# MotorController.net
KiCad netlist of a schematic drawn in EAGLE
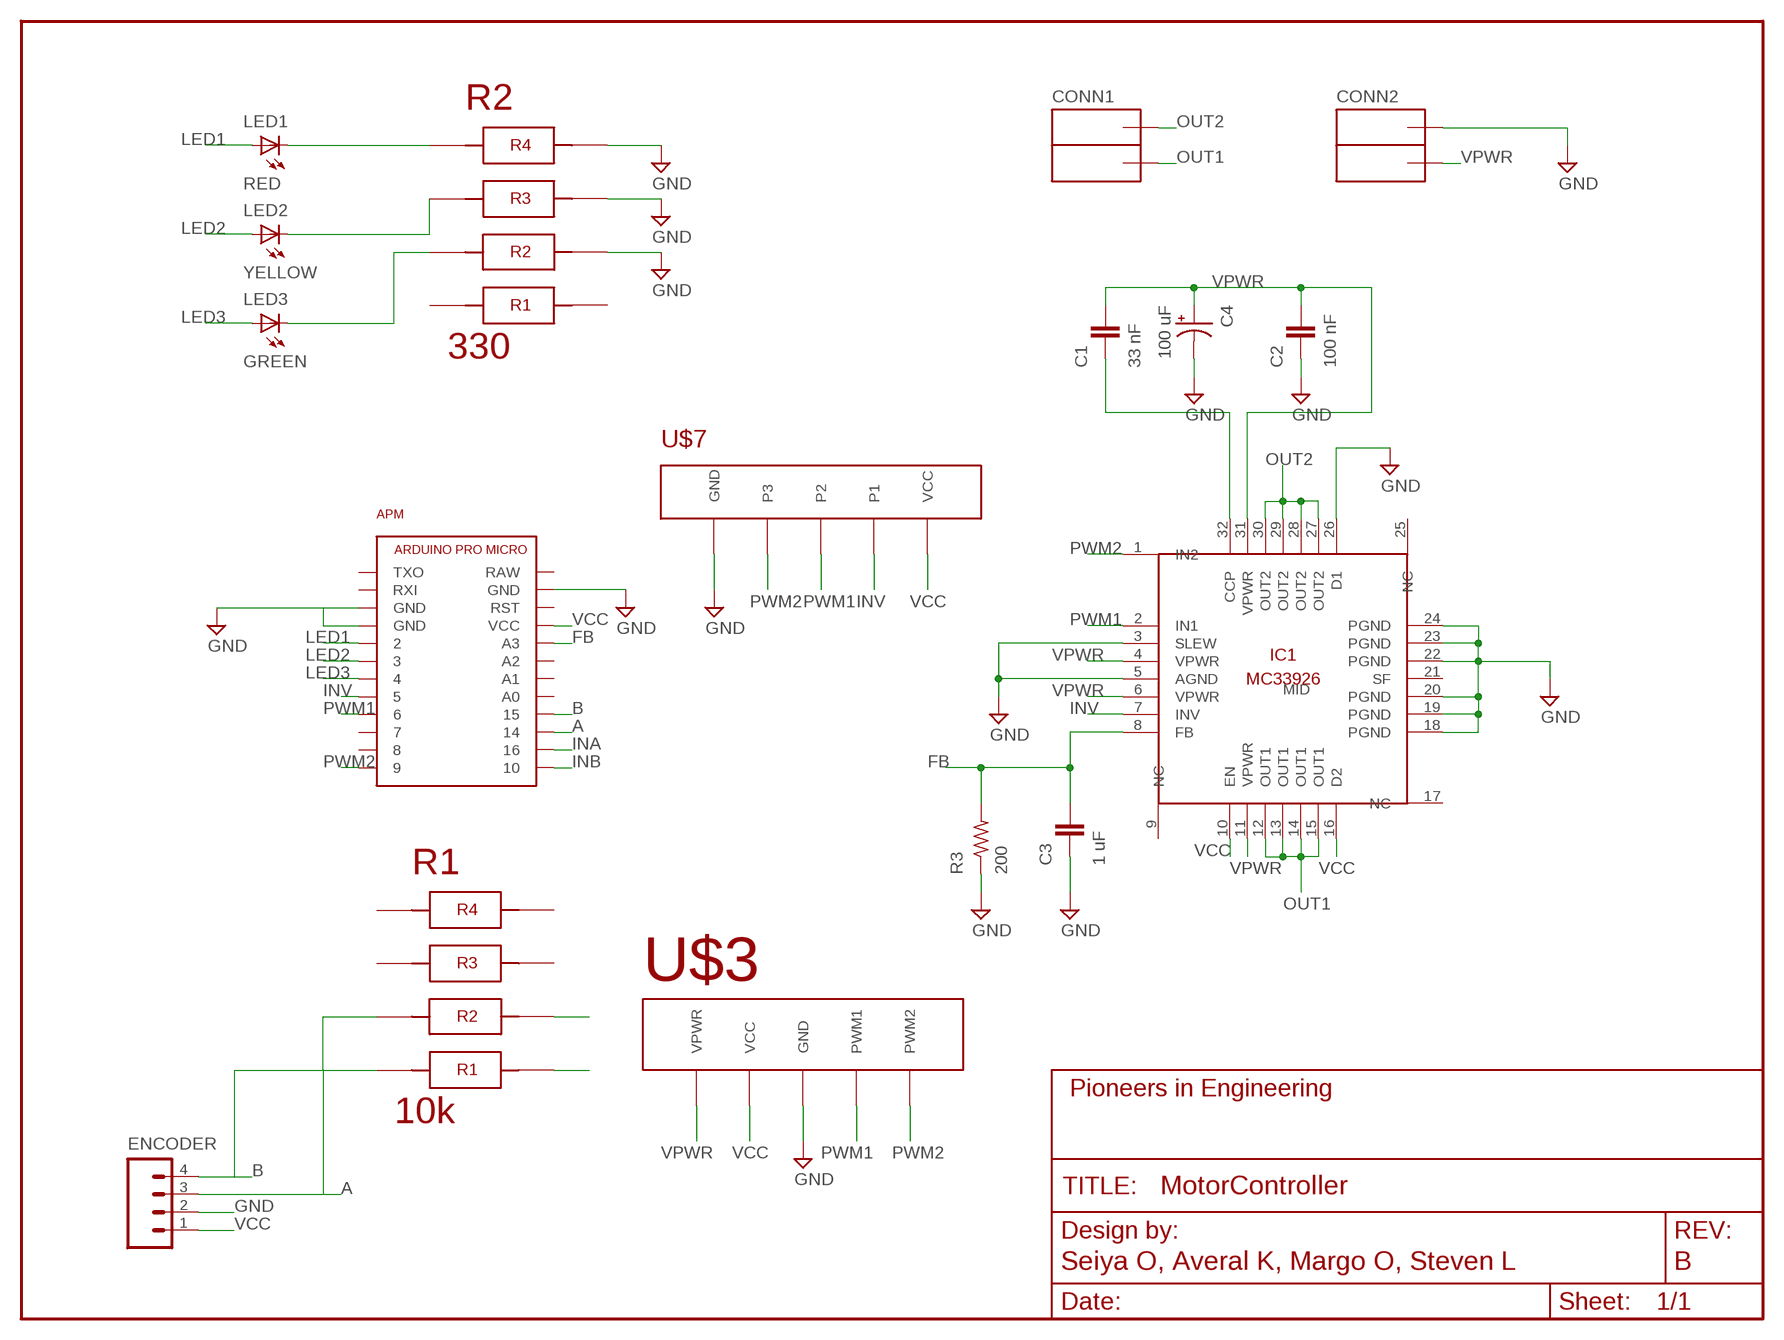
[diagram p0: schematic, sheet 1]

(export (version "E")
  (design (tool "Eeschema 10.0.6"))
  (components
    (comp (ref "APM")
      (value "ARDUINO_PRO_MICRO")
      (footprint "eagle-import:ARDUINO_PRO_MICRO")
      (fields
        (field (name "DISTRIBUTOR_PART_NUMBER") "32284746884")
        (field (name "MANUFACTURER") "Feiyang electronics")
      )
      (libsource (lib "eagle-import") (part "ARDUINO_PRO_MICRO"))
    )
    (comp (ref "C1")
      (value "33 nF")
      (footprint "eagle-import:0603-CAP")
      (libsource (lib "eagle-import") (part "CAP0603-CAP"))
    )
    (comp (ref "C2")
      (value "100 nF")
      (footprint "eagle-import:0603-CAP")
      (libsource (lib "eagle-import") (part "CAP0603-CAP"))
    )
    (comp (ref "C3")
      (value "1 uF")
      (footprint "eagle-import:0603-CAP")
      (libsource (lib "eagle-import") (part "CAP0603-CAP"))
    )
    (comp (ref "C4")
      (value "100 uF")
      (footprint "eagle-import:.248_CAP_THRU")
      (libsource (lib "eagle-import") (part "CAP_POLRADIAL"))
    )
    (comp (ref "CONN1")
      (value "ANDERSONVERTICAL")
      (footprint "eagle-import:ANDERSON_VERTICAL")
      (libsource (lib "eagle-import") (part "ANDERSONVERTICAL"))
    )
    (comp (ref "CONN2")
      (value "ANDERSONVERTICAL")
      (footprint "eagle-import:ANDERSON_VERTICAL")
      (libsource (lib "eagle-import") (part "ANDERSONVERTICAL"))
    )
    (comp (ref "ENCODER")
      (value "M041X04-MTA")
      (footprint "eagle-import:1X04-MTA")
      (libsource (lib "eagle-import") (part "M041X04-MTA"))
    )
    (comp (ref "IC1")
      (value "MC33926")
      (footprint "eagle-import:PQFN-32")
      (libsource (lib "eagle-import") (part "MC33926"))
    )
    (comp (ref "LED1")
      (value "RED")
      (footprint "eagle-import:LED-1206")
      (libsource (lib "eagle-import") (part "LED1206"))
    )
    (comp (ref "LED2")
      (value "YELLOW")
      (footprint "eagle-import:LED-1206")
      (libsource (lib "eagle-import") (part "LED1206"))
    )
    (comp (ref "LED3")
      (value "GREEN")
      (footprint "eagle-import:LED-1206")
      (libsource (lib "eagle-import") (part "LED1206"))
    )
    (comp (ref "R1")
      (value "10k")
      (footprint "eagle-import:4X-0603")
      (libsource (lib "eagle-import") (part "4X-0603"))
    )
    (comp (ref "R2")
      (value "330")
      (footprint "eagle-import:4X-0603")
      (libsource (lib "eagle-import") (part "4X-0603"))
    )
    (comp (ref "R3")
      (value "200")
      (footprint "eagle-import:R0603")
      (fields (field (name "MANUFACTURER") "Rohm Semiconductor"))
      (libsource (lib "eagle-import") (part "R-US_R0603"))
    )
    (comp (ref "U$3")
      (value "5XPOGO")
      (footprint "eagle-import:5XPOGO.40_")
      (libsource (lib "eagle-import") (part "5XPOGO"))
    )
    (comp (ref "U$7")
      (value "5PIN5PIN_MC")
      (footprint "eagle-import:5PIN_MC")
      (libsource (lib "eagle-import") (part "5PIN5PIN_MC"))
    )
  )
  (nets
    (net (code "1") (name "/A") (class "Default")
      (node (ref "APM") (pin "14") (pinfunction "14_14") (pintype "bidirectional"))
      (node (ref "ENCODER") (pin "3") (pinfunction "3_3") (pintype "passive"))
      (node (ref "R1") (pin "7") (pinfunction "7_7") (pintype "bidirectional"))
    )
    (net (code "2") (name "/B") (class "Default")
      (node (ref "APM") (pin "15") (pinfunction "15_15") (pintype "bidirectional"))
      (node (ref "ENCODER") (pin "4") (pinfunction "4_4") (pintype "passive"))
      (node (ref "R1") (pin "8") (pinfunction "8_8") (pintype "bidirectional"))
    )
    (net (code "3") (name "/FB") (class "Default")
      (node (ref "APM") (pin "A3") (pinfunction "A3_A3") (pintype "bidirectional"))
      (node (ref "C3") (pin "2") (pinfunction "2_2") (pintype "passive"))
      (node (ref "IC1") (pin "8") (pinfunction "FB_8") (pintype "bidirectional"))
      (node (ref "R3") (pin "2") (pinfunction "2_2") (pintype "passive"))
    )
    (net (code "4") (name "/INA") (class "Default")
      (node (ref "APM") (pin "16") (pinfunction "16_16") (pintype "bidirectional"))
    )
    (net (code "5") (name "/INB") (class "Default")
      (node (ref "APM") (pin "10") (pinfunction "10_10") (pintype "bidirectional"))
    )
    (net (code "6") (name "/INV") (class "Default")
      (node (ref "APM") (pin "5") (pinfunction "5_5") (pintype "bidirectional"))
      (node (ref "IC1") (pin "7") (pinfunction "INV_7") (pintype "bidirectional"))
      (node (ref "U$7") (pin "INV") (pinfunction "P1_INV") (pintype "bidirectional"))
    )
    (net (code "7") (name "/LED1") (class "Default")
      (node (ref "APM") (pin "2") (pinfunction "2_2") (pintype "bidirectional"))
      (node (ref "LED1") (pin "A") (pinfunction "A_A") (pintype "passive"))
    )
    (net (code "8") (name "/LED2") (class "Default")
      (node (ref "APM") (pin "3") (pinfunction "3_3") (pintype "bidirectional"))
      (node (ref "LED2") (pin "A") (pinfunction "A_A") (pintype "passive"))
    )
    (net (code "9") (name "/LED3") (class "Default")
      (node (ref "APM") (pin "4") (pinfunction "4_4") (pintype "bidirectional"))
      (node (ref "LED3") (pin "A") (pinfunction "A_A") (pintype "passive"))
    )
    (net (code "10") (name "/OUT1") (class "Default")
      (node (ref "CONN1") (pin "PIN1") (pinfunction "OUTB_PIN1") (pintype "bidirectional"))
      (node (ref "IC1") (pin "12") (pinfunction "OUT1_12") (pintype "bidirectional"))
      (node (ref "IC1") (pin "13") (pinfunction "OUT1_13") (pintype "bidirectional"))
      (node (ref "IC1") (pin "14") (pinfunction "OUT1_14") (pintype "bidirectional"))
      (node (ref "IC1") (pin "15") (pinfunction "OUT1_15") (pintype "bidirectional"))
    )
    (net (code "11") (name "/OUT2") (class "Default")
      (node (ref "CONN1") (pin "PIN2") (pinfunction "OUTA_PIN2") (pintype "bidirectional"))
      (node (ref "IC1") (pin "27") (pinfunction "OUT2_27") (pintype "bidirectional"))
      (node (ref "IC1") (pin "28") (pinfunction "OUT2_28") (pintype "bidirectional"))
      (node (ref "IC1") (pin "29") (pinfunction "OUT2_29") (pintype "bidirectional"))
      (node (ref "IC1") (pin "30") (pinfunction "OUT2_30") (pintype "bidirectional"))
    )
    (net (code "12") (name "/PWM1") (class "Default")
      (node (ref "APM") (pin "6") (pinfunction "6_6") (pintype "bidirectional"))
      (node (ref "IC1") (pin "2") (pinfunction "IN1_2") (pintype "bidirectional"))
      (node (ref "U$3") (pin "PWM1") (pinfunction "PWM1_PWM1") (pintype "bidirectional"))
      (node (ref "U$7") (pin "PWM1") (pinfunction "P2_PWM1") (pintype "bidirectional"))
    )
    (net (code "13") (name "/PWM2") (class "Default")
      (node (ref "APM") (pin "9") (pinfunction "9_9") (pintype "bidirectional"))
      (node (ref "IC1") (pin "1") (pinfunction "IN2_1") (pintype "bidirectional"))
      (node (ref "U$3") (pin "PWM2") (pinfunction "PWM2_PWM2") (pintype "bidirectional"))
      (node (ref "U$7") (pin "PWM2") (pinfunction "P3_PWM2") (pintype "bidirectional"))
    )
    (net (code "14") (name "/VCC") (class "Default")
      (node (ref "APM") (pin "VCC") (pinfunction "VCC_VCC") (pintype "bidirectional"))
      (node (ref "ENCODER") (pin "1") (pinfunction "1_1") (pintype "passive"))
      (node (ref "IC1") (pin "10") (pinfunction "EN_10") (pintype "bidirectional"))
      (node (ref "IC1") (pin "16") (pinfunction "D2_16") (pintype "bidirectional"))
      (node (ref "R1") (pin "1") (pinfunction "1_1") (pintype "bidirectional"))
      (node (ref "R1") (pin "2") (pinfunction "2_2") (pintype "bidirectional"))
      (node (ref "U$3") (pin "VCC") (pinfunction "VCC_VCC") (pintype "bidirectional"))
      (node (ref "U$7") (pin "VCC") (pinfunction "VCC_VCC") (pintype "bidirectional"))
    )
    (net (code "15") (name "/VPWR") (class "Default")
      (node (ref "C1") (pin "2") (pinfunction "2_2") (pintype "passive"))
      (node (ref "C2") (pin "2") (pinfunction "2_2") (pintype "passive"))
      (node (ref "C4") (pin "PLUS") (pinfunction "+_PLUS") (pintype "passive"))
      (node (ref "CONN2") (pin "PIN1") (pinfunction "OUTB_PIN1") (pintype "bidirectional"))
      (node (ref "IC1") (pin "11") (pinfunction "VPWR_11") (pintype "bidirectional"))
      (node (ref "IC1") (pin "31") (pinfunction "VPWR_31") (pintype "bidirectional"))
      (node (ref "IC1") (pin "4") (pinfunction "VPWR_4") (pintype "bidirectional"))
      (node (ref "IC1") (pin "6") (pinfunction "VPWR_6") (pintype "bidirectional"))
      (node (ref "U$3") (pin "VPWR") (pinfunction "VPWR_VPWR") (pintype "bidirectional"))
    )
    (net (code "16") (name "GND") (class "Default")
      (node (ref "APM") (pin "GND@0") (pinfunction "GND_GND@0") (pintype "bidirectional"))
      (node (ref "APM") (pin "GND@1") (pinfunction "GND_GND@1") (pintype "bidirectional"))
      (node (ref "APM") (pin "GND@2") (pinfunction "GND_GND@2") (pintype "bidirectional"))
      (node (ref "C2") (pin "1") (pinfunction "1_1") (pintype "passive"))
      (node (ref "C3") (pin "1") (pinfunction "1_1") (pintype "passive"))
      (node (ref "C4") (pin "MINUS") (pinfunction "-_MINUS") (pintype "passive"))
      (node (ref "CONN2") (pin "PIN2") (pinfunction "OUTA_PIN2") (pintype "bidirectional"))
      (node (ref "ENCODER") (pin "2") (pinfunction "2_2") (pintype "passive"))
      (node (ref "IC1") (pin "18") (pinfunction "PGND_18") (pintype "bidirectional"))
      (node (ref "IC1") (pin "19") (pinfunction "PGND_19") (pintype "bidirectional"))
      (node (ref "IC1") (pin "20") (pinfunction "PGND_20") (pintype "bidirectional"))
      (node (ref "IC1") (pin "22") (pinfunction "PGND_22") (pintype "bidirectional"))
      (node (ref "IC1") (pin "23") (pinfunction "PGND_23") (pintype "bidirectional"))
      (node (ref "IC1") (pin "24") (pinfunction "PGND_24") (pintype "bidirectional"))
      (node (ref "IC1") (pin "26") (pinfunction "D1_26") (pintype "bidirectional"))
      (node (ref "IC1") (pin "3") (pinfunction "SLEW_3") (pintype "bidirectional"))
      (node (ref "IC1") (pin "5") (pinfunction "AGND_5") (pintype "bidirectional"))
      (node (ref "R2") (pin "2") (pinfunction "2_2") (pintype "bidirectional"))
      (node (ref "R2") (pin "3") (pinfunction "3_3") (pintype "bidirectional"))
      (node (ref "R2") (pin "4") (pinfunction "4_4") (pintype "bidirectional"))
      (node (ref "R3") (pin "1") (pinfunction "1_1") (pintype "passive"))
      (node (ref "U$3") (pin "GND") (pinfunction "GND_GND") (pintype "bidirectional"))
      (node (ref "U$7") (pin "GND") (pinfunction "GND_GND") (pintype "bidirectional"))
    )
    (net (code "17") (name "Net-(IC1-CCP)") (class "Default")
      (node (ref "C1") (pin "1") (pinfunction "1_1") (pintype "passive"))
      (node (ref "IC1") (pin "32") (pinfunction "CCP_32") (pintype "bidirectional"))
    )
    (net (code "18") (name "Net-(LED1-PadC)") (class "Default")
      (node (ref "LED1") (pin "C") (pinfunction "C_C") (pintype "passive"))
      (node (ref "R2") (pin "5") (pinfunction "5_5") (pintype "bidirectional"))
    )
    (net (code "19") (name "Net-(LED2-PadC)") (class "Default")
      (node (ref "LED2") (pin "C") (pinfunction "C_C") (pintype "passive"))
      (node (ref "R2") (pin "6") (pinfunction "6_6") (pintype "bidirectional"))
    )
    (net (code "20") (name "Net-(LED3-PadC)") (class "Default")
      (node (ref "LED3") (pin "C") (pinfunction "C_C") (pintype "passive"))
      (node (ref "R2") (pin "7") (pinfunction "7_7") (pintype "bidirectional"))
    )
    (net (code "21") (name "unconnected-(APM-Pad7)") (class "Default")
      (node (ref "APM") (pin "7") (pinfunction "7_7") (pintype "bidirectional"))
    )
    (net (code "22") (name "unconnected-(APM-Pad8)") (class "Default")
      (node (ref "APM") (pin "8") (pinfunction "8_8") (pintype "bidirectional"))
    )
    (net (code "23") (name "unconnected-(APM-PadA0)") (class "Default")
      (node (ref "APM") (pin "A0") (pinfunction "A0_A0") (pintype "bidirectional"))
    )
    (net (code "24") (name "unconnected-(APM-PadA1)") (class "Default")
      (node (ref "APM") (pin "A1") (pinfunction "A1_A1") (pintype "bidirectional"))
    )
    (net (code "25") (name "unconnected-(APM-PadA2)") (class "Default")
      (node (ref "APM") (pin "A2") (pinfunction "A2_A2") (pintype "bidirectional"))
    )
    (net (code "26") (name "unconnected-(APM-PadRAW)") (class "Default")
      (node (ref "APM") (pin "RAW") (pinfunction "RAW_RAW") (pintype "bidirectional"))
    )
    (net (code "27") (name "unconnected-(APM-PadRST)") (class "Default")
      (node (ref "APM") (pin "RST") (pinfunction "RST_RST") (pintype "bidirectional"))
    )
    (net (code "28") (name "unconnected-(APM-PadRXI)") (class "Default")
      (node (ref "APM") (pin "RXI") (pinfunction "RXI_RXI") (pintype "bidirectional"))
    )
    (net (code "29") (name "unconnected-(APM-PadTXO)") (class "Default")
      (node (ref "APM") (pin "TXO") (pinfunction "TXO_TXO") (pintype "bidirectional"))
    )
    (net (code "30") (name "unconnected-(IC1-AGND-PadMID)") (class "Default")
      (node (ref "IC1") (pin "MID") (pinfunction "AGND_MID") (pintype "bidirectional"))
    )
    (net (code "31") (name "unconnected-(IC1-NC-Pad9)") (class "Default")
      (node (ref "IC1") (pin "9") (pinfunction "NC_9") (pintype "bidirectional"))
    )
    (net (code "32") (name "unconnected-(IC1-NC-Pad17)") (class "Default")
      (node (ref "IC1") (pin "17") (pinfunction "NC_17") (pintype "bidirectional"))
    )
    (net (code "33") (name "unconnected-(IC1-NC-Pad25)") (class "Default")
      (node (ref "IC1") (pin "25") (pinfunction "NC_25") (pintype "bidirectional"))
    )
    (net (code "34") (name "unconnected-(IC1-SF-Pad21)") (class "Default")
      (node (ref "IC1") (pin "21") (pinfunction "SF_21") (pintype "bidirectional"))
    )
    (net (code "35") (name "unconnected-(R1-Pad3)") (class "Default")
      (node (ref "R1") (pin "3") (pinfunction "3_3") (pintype "bidirectional"))
    )
    (net (code "36") (name "unconnected-(R1-Pad4)") (class "Default")
      (node (ref "R1") (pin "4") (pinfunction "4_4") (pintype "bidirectional"))
    )
    (net (code "37") (name "unconnected-(R1-Pad5)") (class "Default")
      (node (ref "R1") (pin "5") (pinfunction "5_5") (pintype "bidirectional"))
    )
    (net (code "38") (name "unconnected-(R1-Pad6)") (class "Default")
      (node (ref "R1") (pin "6") (pinfunction "6_6") (pintype "bidirectional"))
    )
    (net (code "39") (name "unconnected-(R2-Pad1)") (class "Default")
      (node (ref "R2") (pin "1") (pinfunction "1_1") (pintype "bidirectional"))
    )
    (net (code "40") (name "unconnected-(R2-Pad8)") (class "Default")
      (node (ref "R2") (pin "8") (pinfunction "8_8") (pintype "bidirectional"))
    )
  )
)
